# Display_Segmental_LCD118x1_DF700543-05_B.net
KiCad netlist of a schematic drawn in Altium Designer
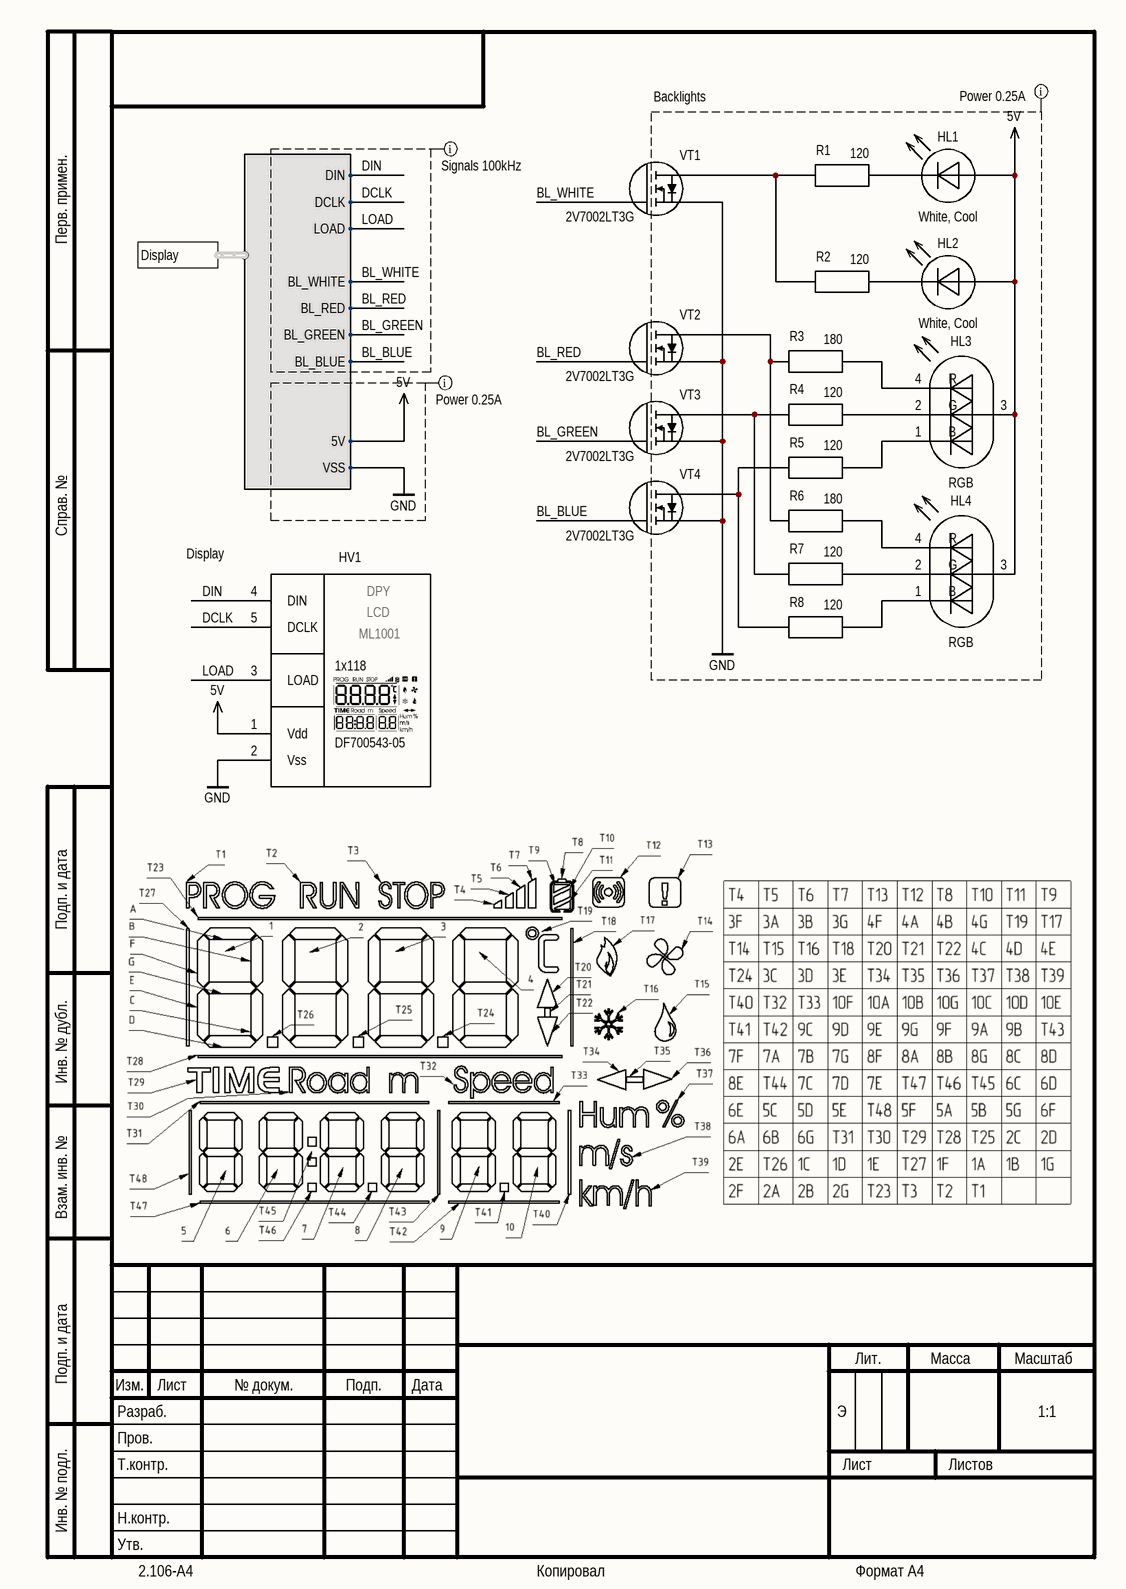
[diagram p0: Display Segmental LCD118x1 DF700543-05 Backlights RGBW.SchDoc]

(export (version "E")
  (design (tool "Eeschema 10.0.6"))
  (components
    (comp (ref "HL1")
      (value "White, Cool")
      (footprint "LED 3216 RA")
      (description "LED White 1206(3216) RA")
      (fields (field (name "MANUFACTURER") "Harvatek"))
      (libsource (lib "LED") (part "HQ12-2152UWC"))
    )
    (comp (ref "HL2")
      (value "White, Cool")
      (footprint "LED 3216 RA")
      (description "LED White 1206(3216) RA")
      (fields (field (name "MANUFACTURER") "Harvatek"))
      (libsource (lib "LED") (part "HQ12-2152UWC"))
    )
    (comp (ref "HL3")
      (value "RGB")
      (footprint "LED RGB 3216 RA")
      (description "LED RGB 1206(3216) RA CA")
      (fields (field (name "MANUFACTURER") "Harvatek"))
      (libsource (lib "LED") (part "HQ12-2353RGBC"))
    )
    (comp (ref "HL4")
      (value "RGB")
      (footprint "LED RGB 3216 RA")
      (description "LED RGB 1206(3216) RA CA")
      (fields (field (name "MANUFACTURER") "Harvatek"))
      (libsource (lib "LED") (part "HQ12-2353RGBC"))
    )
    (comp (ref "HV1")
      (value "DF700543-05")
      (footprint "DISP SEG LCD128 DF700543-05")
      (description "Display Segmental LCD128 Special")
      (libsource (lib "Displays") (part "DF700543-05"))
    )
    (comp (ref "R1")
      (value "120")
      (footprint "RESC1608M")
      (description "RESC 120 0603(1608)")
      (fields (field (name "MANUFACTURER") "Yageo") (field (name "TOLERANCE") "±5%"))
      (libsource (lib "Resistors Ceramic SMD") (part "RC0603JR-07120RL"))
    )
    (comp (ref "R2")
      (value "120")
      (footprint "RESC1608M")
      (description "RESC 120 0603(1608)")
      (fields (field (name "MANUFACTURER") "Yageo") (field (name "TOLERANCE") "±5%"))
      (libsource (lib "Resistors Ceramic SMD") (part "RC0603JR-07120RL"))
    )
    (comp (ref "R3")
      (value "180")
      (footprint "RESC1608M")
      (description "RESC 180 0603(1608)")
      (fields (field (name "MANUFACTURER") "Yageo") (field (name "TOLERANCE") "±5%"))
      (libsource (lib "Resistors Ceramic SMD") (part "RC0603JR-07180RL"))
    )
    (comp (ref "R4")
      (value "120")
      (footprint "RESC1608M")
      (description "RESC 120 0603(1608)")
      (fields (field (name "MANUFACTURER") "Yageo") (field (name "TOLERANCE") "±5%"))
      (libsource (lib "Resistors Ceramic SMD") (part "RC0603JR-07120RL"))
    )
    (comp (ref "R5")
      (value "120")
      (footprint "RESC1608M")
      (description "RESC 120 0603(1608)")
      (fields (field (name "MANUFACTURER") "Yageo") (field (name "TOLERANCE") "±5%"))
      (libsource (lib "Resistors Ceramic SMD") (part "RC0603JR-07120RL"))
    )
    (comp (ref "R6")
      (value "180")
      (footprint "RESC1608M")
      (description "RESC 180 0603(1608)")
      (fields (field (name "MANUFACTURER") "Yageo") (field (name "TOLERANCE") "±5%"))
      (libsource (lib "Resistors Ceramic SMD") (part "RC0603JR-07180RL"))
    )
    (comp (ref "R7")
      (value "120")
      (footprint "RESC1608M")
      (description "RESC 120 0603(1608)")
      (fields (field (name "MANUFACTURER") "Yageo") (field (name "TOLERANCE") "±5%"))
      (libsource (lib "Resistors Ceramic SMD") (part "RC0603JR-07120RL"))
    )
    (comp (ref "R8")
      (value "120")
      (footprint "RESC1608M")
      (description "RESC 120 0603(1608)")
      (fields (field (name "MANUFACTURER") "Yageo") (field (name "TOLERANCE") "±5%"))
      (libsource (lib "Resistors Ceramic SMD") (part "RC0603JR-07120RL"))
    )
    (comp (ref "VT1")
      (value "2V7002LT3G")
      (footprint "SOT-23-3M")
      (description "MOSFET N 0.1A 60V")
      (fields (field (name "MANUFACTURER") "ON Semiconductor"))
      (libsource (lib "Transistors") (part "2V7002LT3G"))
    )
    (comp (ref "VT2")
      (value "2V7002LT3G")
      (footprint "SOT-23-3M")
      (description "MOSFET N 0.1A 60V")
      (fields (field (name "MANUFACTURER") "ON Semiconductor"))
      (libsource (lib "Transistors") (part "2V7002LT3G"))
    )
    (comp (ref "VT3")
      (value "2V7002LT3G")
      (footprint "SOT-23-3M")
      (description "MOSFET N 0.1A 60V")
      (fields (field (name "MANUFACTURER") "ON Semiconductor"))
      (libsource (lib "Transistors") (part "2V7002LT3G"))
    )
    (comp (ref "VT4")
      (value "2V7002LT3G")
      (footprint "SOT-23-3M")
      (description "MOSFET N 0.1A 60V")
      (fields (field (name "MANUFACTURER") "ON Semiconductor"))
      (libsource (lib "Transistors") (part "2V7002LT3G"))
    )
  )
  (nets
    (net (code "2") (name "/BL_BLUE") (class "Default")
      (node (ref "VT4") (pin "1") (pinfunction "Gate_1") (pintype "passive"))
    )
    (net (code "3") (name "/BL_GREEN") (class "Default")
      (node (ref "VT3") (pin "1") (pinfunction "Gate_1") (pintype "passive"))
    )
    (net (code "4") (name "/BL_RED") (class "Default")
      (node (ref "VT2") (pin "1") (pinfunction "Gate_1") (pintype "passive"))
    )
    (net (code "5") (name "/BL_WHITE") (class "Default")
      (node (ref "VT1") (pin "1") (pinfunction "Gate_1") (pintype "passive"))
    )
    (net (code "6") (name "/DCLK") (class "Default")
      (node (ref "HV1") (pin "5") (pinfunction "DCLK_5") (pintype "passive"))
    )
    (net (code "7") (name "/DIN") (class "Default")
      (node (ref "HV1") (pin "4") (pinfunction "DIN_4") (pintype "passive"))
    )
    (net (code "8") (name "/LOAD") (class "Default")
      (node (ref "HV1") (pin "3") (pinfunction "LOAD_3") (pintype "passive"))
    )
    (net (code "10") (name "5V") (class "Default")
      (node (ref "HL1") (pin "1") (pinfunction "Anode_1") (pintype "passive"))
      (node (ref "HL2") (pin "1") (pinfunction "Anode_1") (pintype "passive"))
      (node (ref "HL3") (pin "3") (pinfunction "CA_3") (pintype "passive"))
      (node (ref "HL4") (pin "3") (pinfunction "CA_3") (pintype "passive"))
      (node (ref "HV1") (pin "1") (pinfunction "Vdd_1") (pintype "passive"))
    )
    (net (code "11") (name "GND") (class "Default")
      (node (ref "HV1") (pin "2") (pinfunction "Vss_2") (pintype "passive"))
      (node (ref "VT1") (pin "2") (pinfunction "Source_2") (pintype "passive"))
      (node (ref "VT2") (pin "2") (pinfunction "Source_2") (pintype "passive"))
      (node (ref "VT3") (pin "2") (pinfunction "Source_2") (pintype "passive"))
      (node (ref "VT4") (pin "2") (pinfunction "Source_2") (pintype "passive"))
    )
    (net (code "12") (name "Net-(HL1-Cathode)") (class "Default")
      (node (ref "HL1") (pin "2") (pinfunction "Cathode_2") (pintype "passive"))
      (node (ref "R1") (pin "2") (pinfunction "2_2") (pintype "passive"))
    )
    (net (code "13") (name "Net-(HL2-Cathode)") (class "Default")
      (node (ref "HL2") (pin "2") (pinfunction "Cathode_2") (pintype "passive"))
      (node (ref "R2") (pin "2") (pinfunction "2_2") (pintype "passive"))
    )
    (net (code "14") (name "Net-(HL3-BLUE)") (class "Default")
      (node (ref "HL3") (pin "1") (pinfunction "BLUE_1") (pintype "passive"))
      (node (ref "R5") (pin "2") (pinfunction "2_2") (pintype "passive"))
    )
    (net (code "15") (name "Net-(HL3-GREEN)") (class "Default")
      (node (ref "HL3") (pin "2") (pinfunction "GREEN_2") (pintype "passive"))
      (node (ref "R4") (pin "2") (pinfunction "2_2") (pintype "passive"))
    )
    (net (code "16") (name "Net-(HL3-RED)") (class "Default")
      (node (ref "HL3") (pin "4") (pinfunction "RED_4") (pintype "passive"))
      (node (ref "R3") (pin "2") (pinfunction "2_2") (pintype "passive"))
    )
    (net (code "17") (name "Net-(HL4-BLUE)") (class "Default")
      (node (ref "HL4") (pin "1") (pinfunction "BLUE_1") (pintype "passive"))
      (node (ref "R8") (pin "2") (pinfunction "2_2") (pintype "passive"))
    )
    (net (code "18") (name "Net-(HL4-GREEN)") (class "Default")
      (node (ref "HL4") (pin "2") (pinfunction "GREEN_2") (pintype "passive"))
      (node (ref "R7") (pin "2") (pinfunction "2_2") (pintype "passive"))
    )
    (net (code "19") (name "Net-(HL4-RED)") (class "Default")
      (node (ref "HL4") (pin "4") (pinfunction "RED_4") (pintype "passive"))
      (node (ref "R6") (pin "2") (pinfunction "2_2") (pintype "passive"))
    )
    (net (code "20") (name "Net-(VT1-Drain)") (class "Default")
      (node (ref "R1") (pin "1") (pinfunction "1_1") (pintype "passive"))
      (node (ref "R2") (pin "1") (pinfunction "1_1") (pintype "passive"))
      (node (ref "VT1") (pin "3") (pinfunction "Drain_3") (pintype "passive"))
    )
    (net (code "21") (name "Net-(VT2-Drain)") (class "Default")
      (node (ref "R3") (pin "1") (pinfunction "1_1") (pintype "passive"))
      (node (ref "R6") (pin "1") (pinfunction "1_1") (pintype "passive"))
      (node (ref "VT2") (pin "3") (pinfunction "Drain_3") (pintype "passive"))
    )
    (net (code "22") (name "Net-(VT3-Drain)") (class "Default")
      (node (ref "R4") (pin "1") (pinfunction "1_1") (pintype "passive"))
      (node (ref "R7") (pin "1") (pinfunction "1_1") (pintype "passive"))
      (node (ref "VT3") (pin "3") (pinfunction "Drain_3") (pintype "passive"))
    )
    (net (code "23") (name "Net-(VT4-Drain)") (class "Default")
      (node (ref "R5") (pin "1") (pinfunction "1_1") (pintype "passive"))
      (node (ref "R8") (pin "1") (pinfunction "1_1") (pintype "passive"))
      (node (ref "VT4") (pin "3") (pinfunction "Drain_3") (pintype "passive"))
    )
  )
)
